# Supply.net
KiCad netlist of a schematic drawn in Altium Designer
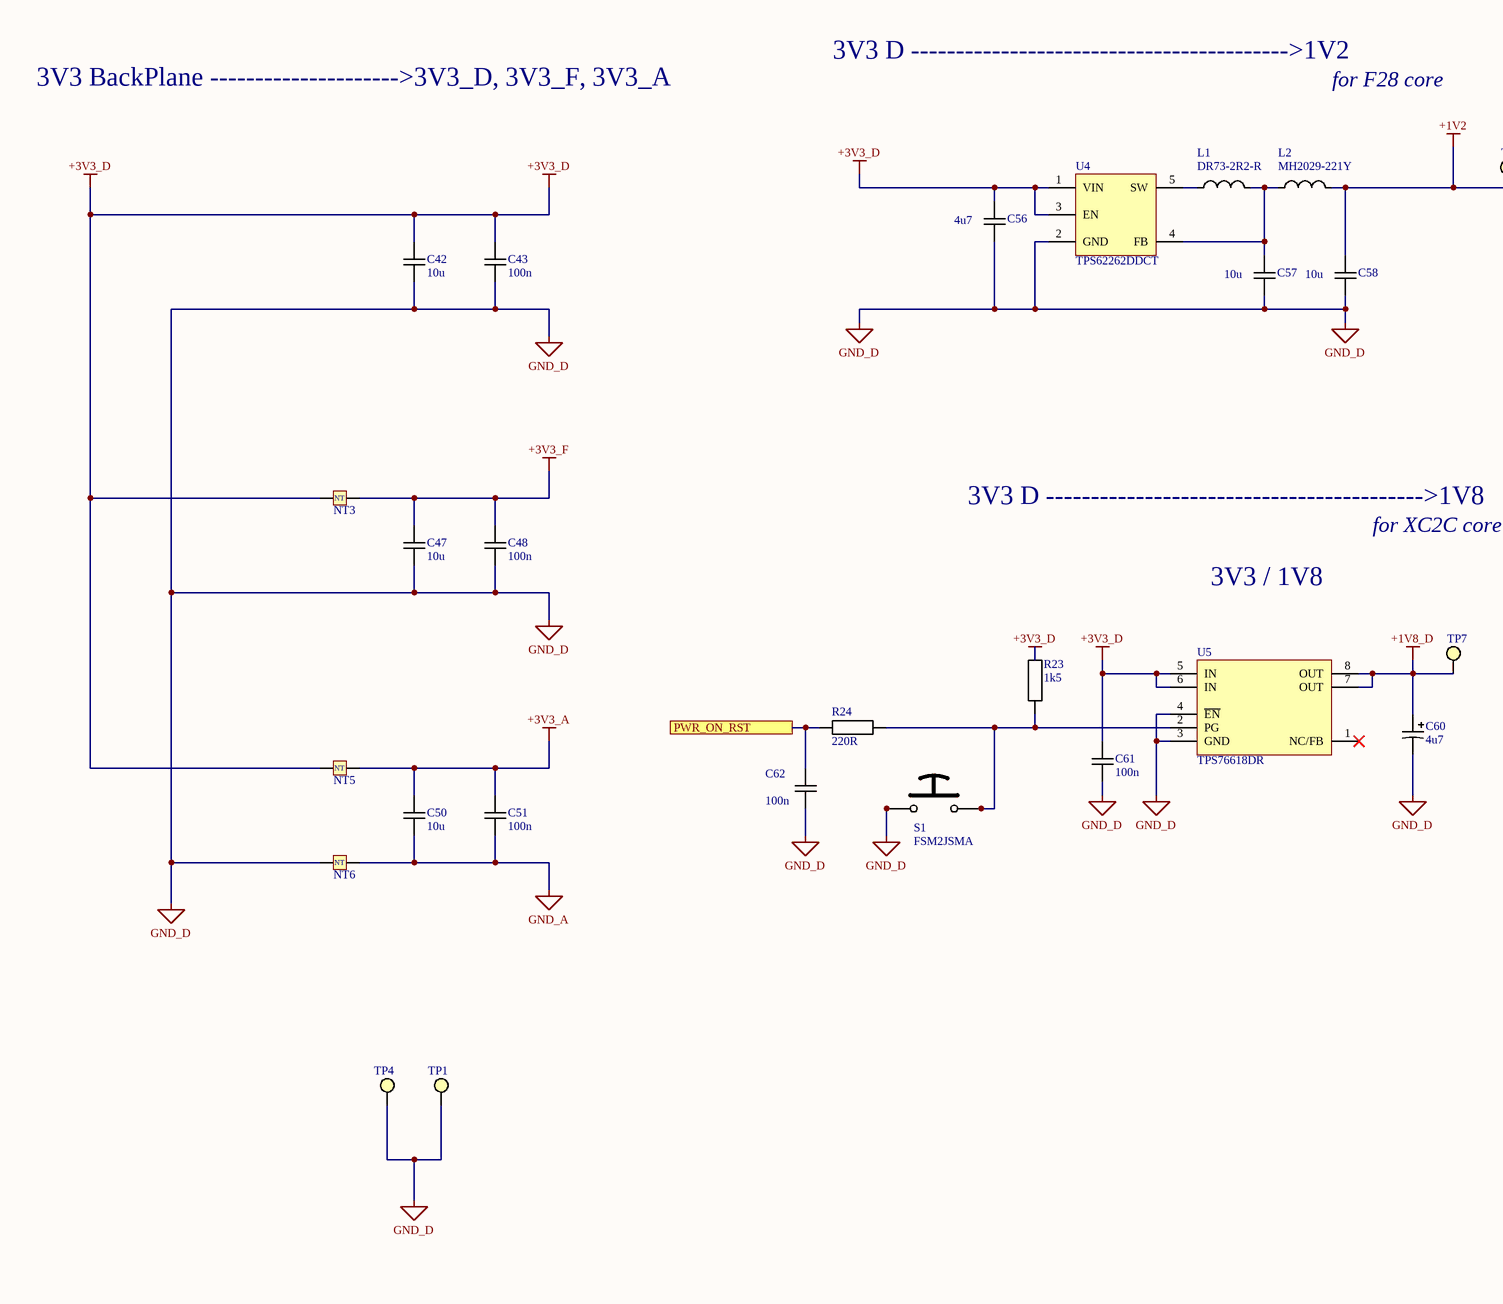
[diagram p0: Supply.SchDoc, left]
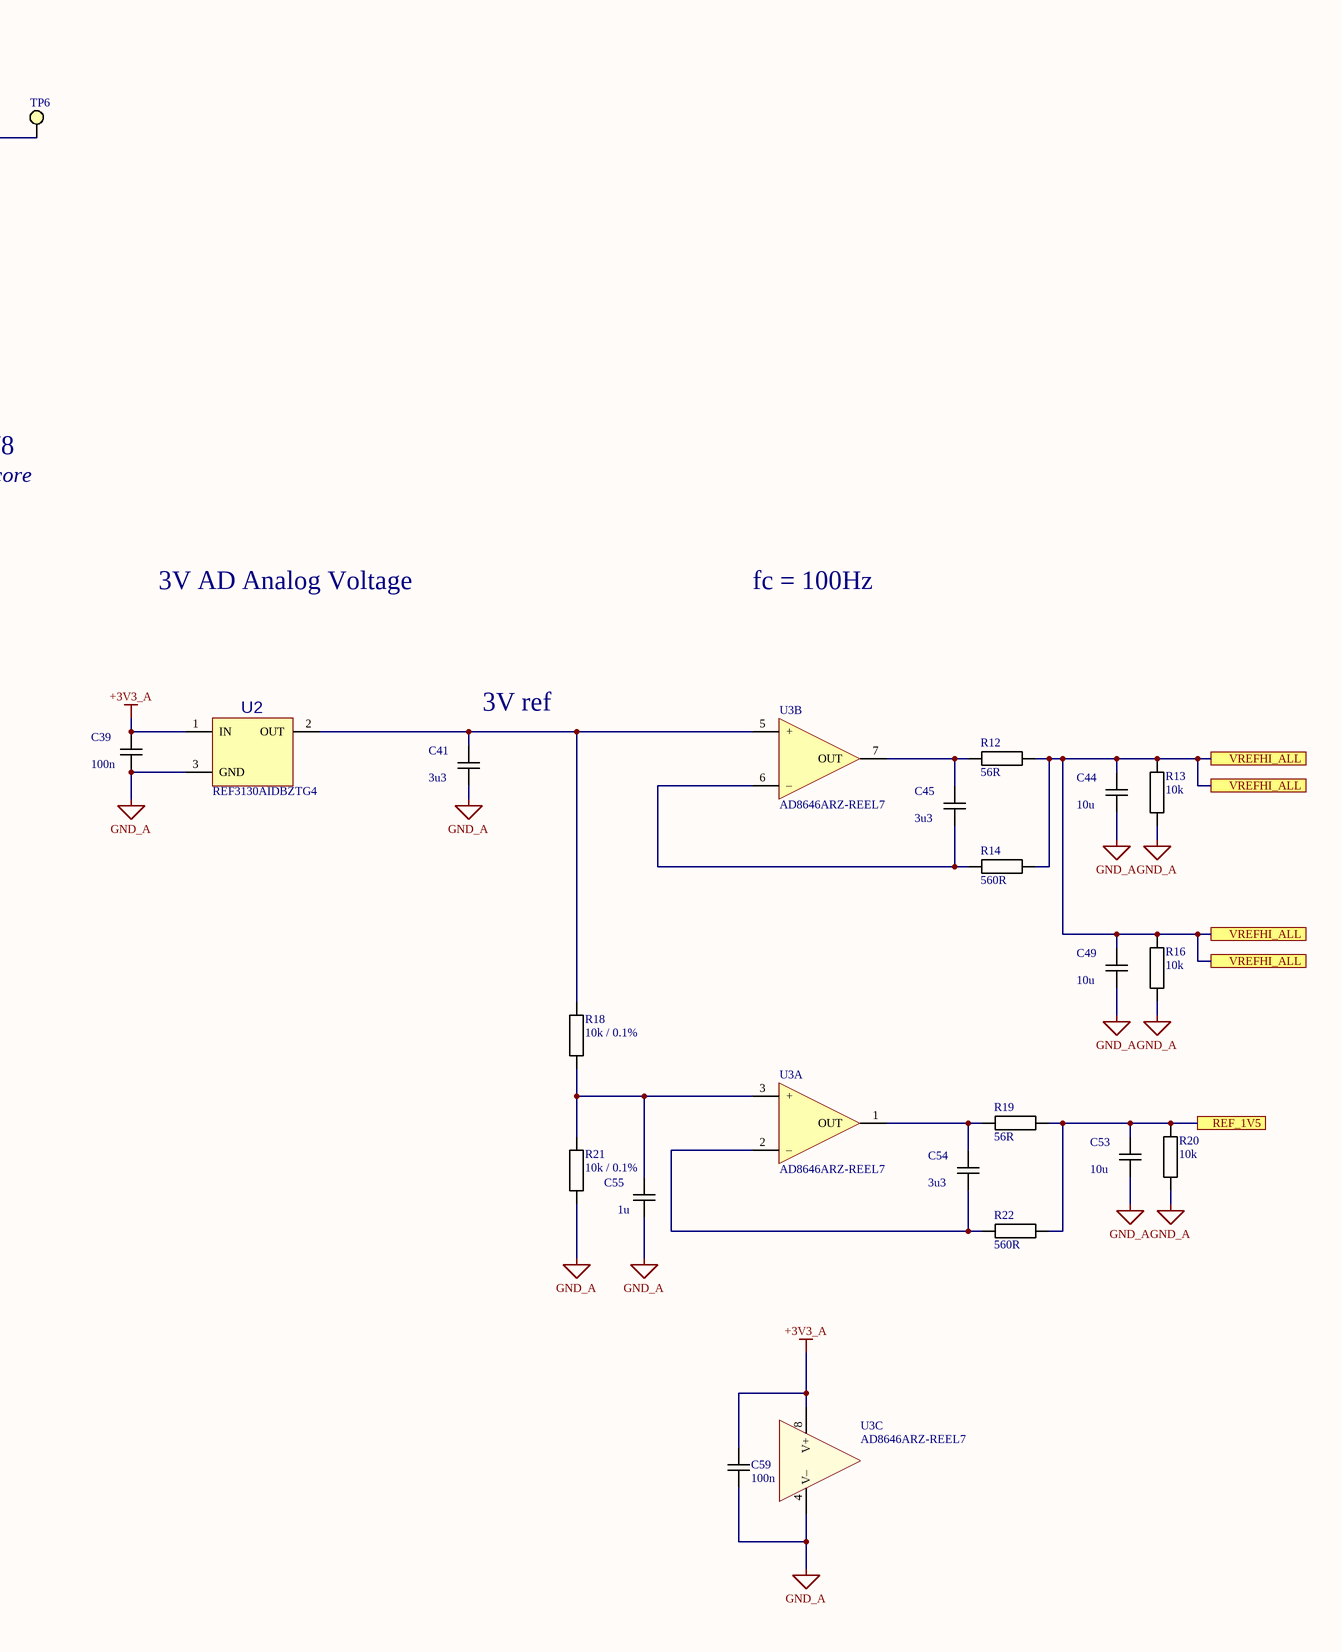
[diagram p1: Supply.SchDoc, right]

(export (version "E")
  (design (tool "Eeschema 10.0.6"))
  (components
    (comp (ref "C39")
      (value "100n")
      (footprint "CAPACITOR 1608 REFLOW")
      (description "Capacitor X7R 10% 50V 1608(0603)")
      (libsource (lib "Capacitor") (part "Capacitor"))
    )
    (comp (ref "C41")
      (value "3u3")
      (footprint "CAPACITOR 2012 REFLOW")
      (description "Capacitor X7R 10% 10V 2012(0805)")
      (libsource (lib "Capacitor") (part "Capacitor"))
    )
    (comp (ref "C42")
      (value "10u")
      (footprint "CAPACITOR 2012 REFLOW")
      (description "Capacitor X7R 10% 10V 2012(0805)")
      (libsource (lib "Capacitor") (part "Capacitor"))
    )
    (comp (ref "C43")
      (value "100n")
      (footprint "CAPACITOR 2012 REFLOW")
      (description "Capacitor X7R 10% 50V 2012(0805)")
      (libsource (lib "Capacitor") (part "Capacitor"))
    )
    (comp (ref "C44")
      (value "10u")
      (footprint "CAPACITOR 2012 REFLOW")
      (description "Capacitor X7R 10% 10V 2012(0805)")
      (libsource (lib "Capacitor") (part "Capacitor"))
    )
    (comp (ref "C45")
      (value "3u3")
      (footprint "CAPACITOR 2012 REFLOW")
      (description "Capacitor X7R 10% 10V 2012(0805)")
      (libsource (lib "Capacitor") (part "Capacitor"))
    )
    (comp (ref "C47")
      (value "10u")
      (footprint "CAPACITOR 2012 REFLOW")
      (description "Capacitor X7R 10% 10V 2012(0805)")
      (libsource (lib "Capacitor") (part "Capacitor"))
    )
    (comp (ref "C48")
      (value "100n")
      (footprint "CAPACITOR 2012 REFLOW")
      (description "Capacitor X7R 10% 50V 2012(0805)")
      (libsource (lib "Capacitor") (part "Capacitor"))
    )
    (comp (ref "C49")
      (value "10u")
      (footprint "CAPACITOR 2012 REFLOW")
      (description "Capacitor X7R 10% 10V 2012(0805)")
      (libsource (lib "Capacitor") (part "Capacitor"))
    )
    (comp (ref "C50")
      (value "10u")
      (footprint "CAPACITOR 2012 REFLOW")
      (description "Capacitor X7R 10% 10V 2012(0805)")
      (libsource (lib "Capacitor") (part "Capacitor"))
    )
    (comp (ref "C51")
      (value "100n")
      (footprint "CAPACITOR 2012 REFLOW")
      (description "Capacitor X7R 10% 50V 2012(0805)")
      (libsource (lib "Capacitor") (part "Capacitor"))
    )
    (comp (ref "C53")
      (value "10u")
      (footprint "CAPACITOR 2012 REFLOW")
      (description "Capacitor X7R 10% 10V 2012(0805)")
      (libsource (lib "Capacitor") (part "Capacitor"))
    )
    (comp (ref "C54")
      (value "3u3")
      (footprint "CAPACITOR 2012 REFLOW")
      (description "Capacitor X7R 10% 10V 2012(0805)")
      (libsource (lib "Capacitor") (part "Capacitor"))
    )
    (comp (ref "C55")
      (value "1u")
      (footprint "CAPACITOR 2012 REFLOW")
      (description "Capacitor X7R 10% 10V 2012(0805)")
      (libsource (lib "Capacitor") (part "Capacitor"))
    )
    (comp (ref "C56")
      (value "4u7")
      (footprint "CAPACITOR 2012 REFLOW")
      (description "Capacitor X7R 10% 10V 2012(0805)")
      (libsource (lib "Capacitor") (part "Capacitor"))
    )
    (comp (ref "C57")
      (value "10u")
      (footprint "CAPACITOR 2012 REFLOW")
      (description "Capacitor X7R 10% 10V 2012(0805)")
      (libsource (lib "Capacitor") (part "Capacitor"))
    )
    (comp (ref "C58")
      (value "10u")
      (footprint "CAPACITOR 2012 REFLOW")
      (description "Capacitor X7R 10% 10V 2012(0805)")
      (libsource (lib "Capacitor") (part "Capacitor"))
    )
    (comp (ref "C59")
      (value "100n")
      (footprint "CAPACITOR 1608 REFLOW")
      (description "Capacitor X7R 10% 50V 1608(0603)")
      (libsource (lib "Capacitor") (part "Capacitor"))
    )
    (comp (ref "C60")
      (value "4u7")
      (footprint "CAPACITOR POL 3528-21 REFLOW")
      (description "Capacitor Tantalum 10 % 10V 3528(1311-TAJ-B)")
      (libsource (lib "Capacitor") (part "Capacitor Polarized"))
    )
    (comp (ref "C61")
      (value "100n")
      (footprint "CAPACITOR 1608 REFLOW")
      (description "Capacitor X7R 10% 50V 1608(0603)")
      (libsource (lib "Capacitor") (part "Capacitor"))
    )
    (comp (ref "C62")
      (value "100n")
      (footprint "CAPACITOR 1608 REFLOW")
      (description "Capacitor X7R 10% 50V 1608(0603)")
      (libsource (lib "Capacitor") (part "Capacitor"))
    )
    (comp (ref "L1")
      (value "DR73-2R2-R")
      (footprint "DR73")
      (description "Inductor")
      (fields (field (name "MANUFACTURER") "Coiltronics / Eaton"))
      (libsource (lib "Inductor") (part "Inductor"))
    )
    (comp (ref "L2")
      (value "MH2029-221Y")
      (footprint "INDUCTOR 2012 REFLOW")
      (description "Inductor")
      (fields (field (name "MANUFACTURER") "Bourns"))
      (libsource (lib "Inductor") (part "Inductor"))
    )
    (comp (ref "NT3")
      (value "Net Tie")
      (footprint "NET TIE 1005")
      (description "Connection for 2 different NETNAME")
      (libsource (lib "Jumper") (part "Net Tie"))
    )
    (comp (ref "NT5")
      (value "Net Tie")
      (footprint "NET TIE 1005")
      (description "Connection for 2 different NETNAME")
      (libsource (lib "Jumper") (part "Net Tie"))
    )
    (comp (ref "NT6")
      (value "Net Tie")
      (footprint "NET TIE 1005")
      (description "Connection for 2 different NETNAME")
      (libsource (lib "Jumper") (part "Net Tie"))
    )
    (comp (ref "R12")
      (value "56R")
      (footprint "RESISTOR 1608 REFLOW")
      (description "Resistor 1% 50V 100mW 1608(0603)")
      (libsource (lib "Resistor") (part "Resistor"))
    )
    (comp (ref "R13")
      (value "10k")
      (footprint "RESISTOR 1608 REFLOW")
      (description "Resistor 1% 50V 100mW 1608(0603)")
      (libsource (lib "Resistor") (part "Resistor"))
    )
    (comp (ref "R14")
      (value "560R")
      (footprint "RESISTOR 1608 REFLOW")
      (description "Resistor 1% 50V 100mW 1608(0603)")
      (libsource (lib "Resistor") (part "Resistor"))
    )
    (comp (ref "R16")
      (value "10k")
      (footprint "RESISTOR 1608 REFLOW")
      (description "Resistor 1% 50V 100mW 1608(0603)")
      (libsource (lib "Resistor") (part "Resistor"))
    )
    (comp (ref "R18")
      (value "10k / 0.1%")
      (footprint "RESISTOR 1608 REFLOW")
      (description "Resistor 1% 50V 100mW 1608(0603)")
      (libsource (lib "Resistor") (part "Resistor"))
    )
    (comp (ref "R19")
      (value "56R")
      (footprint "RESISTOR 1608 REFLOW")
      (description "Resistor 1% 50V 100mW 1608(0603)")
      (libsource (lib "Resistor") (part "Resistor"))
    )
    (comp (ref "R20")
      (value "10k")
      (footprint "RESISTOR 1608 REFLOW")
      (description "Resistor 1% 50V 100mW 1608(0603)")
      (libsource (lib "Resistor") (part "Resistor"))
    )
    (comp (ref "R21")
      (value "10k / 0.1%")
      (footprint "RESISTOR 1608 REFLOW")
      (description "Resistor 1% 50V 100mW 1608(0603)")
      (libsource (lib "Resistor") (part "Resistor"))
    )
    (comp (ref "R22")
      (value "560R")
      (footprint "RESISTOR 1608 REFLOW")
      (description "Resistor 1% 50V 100mW 1608(0603)")
      (libsource (lib "Resistor") (part "Resistor"))
    )
    (comp (ref "R23")
      (value "1k5")
      (footprint "RESISTOR 1608 REFLOW")
      (description "Resistor 1% 50V 100mW 1608(0603)")
      (libsource (lib "Resistor") (part "Resistor"))
    )
    (comp (ref "R24")
      (value "220R")
      (footprint "RESISTOR 1608 REFLOW")
      (description "Resistor 1% 50V 100mW 1608(0603)")
      (libsource (lib "Resistor") (part "Resistor"))
    )
    (comp (ref "S1")
      (value "FSM2JSMA")
      (footprint "Push Button C6.0x6.0 TE FSM-2J-SMA")
      (description "Push Button, 4 pins, 2 poles parrallèle")
      (fields (field (name "MANUFACTURER") "TE Connectivity / Alcoswitch"))
      (libsource (lib "Button") (part "Push Button 4Pins"))
    )
    (comp (ref "TP1")
      (value "*")
      (footprint "Test Point Keystone Miniature BLACK")
      (description "Test Point")
      (libsource (lib "Testpoint") (part "Test Point"))
    )
    (comp (ref "TP4")
      (value "*")
      (footprint "Test Point Keystone Miniature BLACK")
      (description "Test Point")
      (libsource (lib "Testpoint") (part "Test Point"))
    )
    (comp (ref "TP6")
      (value "*")
      (footprint "Hole 1.0 D2.0")
      (description "Hole")
      (libsource (lib "Testpoint") (part "Hole"))
    )
    (comp (ref "TP7")
      (value "*")
      (footprint "Hole 1.0 D2.0")
      (description "Hole")
      (libsource (lib "Testpoint") (part "Hole"))
    )
    (comp (ref "U2")
      (value "REF3130AIDBZTG4")
      (footprint "SOT23 P0.95 C1.6x3.0 H1.3")
      (description "Generic Positive Voltage Reference")
      (fields (field (name "MANUFACTURER") "Texas Instruments"))
      (libsource (lib "Regulator") (part "REFERENCE SOT23 IN-OUT- GND"))
    )
    (comp (ref "U3")
      (value "AD8646ARZ-REEL7")
      (footprint "SO8 P1.27 C4.0X5.0 H1.75")
      (description "Generic dual OPA 8 pins")
      (fields (field (name "MANUFACTURER") "Analog Devices"))
      (libsource (lib "Amplifier") (part "OPA DUAL"))
    )
    (comp (ref "U4")
      (value "TPS62262DDCT")
      (footprint "SOT23-5 P0.95 C1.6x3.0 H1.3")
      (description "2.25-MHz 600-mA Step Down Converter in 2 x 2 SOT Package")
      (fields (field (name "MANUFACTURER") "Texas Instruments"))
      (libsource (lib "VoltageConverter") (part "TPS6226x"))
    )
    (comp (ref "U5")
      (value "TPS76618DR")
      (footprint "SO8 P1.27 C4.0X5.0 H1.75")
      (description "Ultra Low Quiescent Current 250mA, Low Dropout Regulator")
      (fields (field (name "MANUFACTURER") "Texas Instruments"))
      (libsource (lib "Regulator") (part "TPS766__D"))
    )
  )
  (nets
    (net (code "1") (name "+1V2") (class "Default")
      (node (ref "C58") (pin "2") (pinfunction "2_2") (pintype "passive"))
      (node (ref "L2") (pin "2") (pinfunction "2_2") (pintype "passive"))
      (node (ref "TP6") (pin "1") (pinfunction "1_1") (pintype "passive"))
    )
    (net (code "2") (name "+1V8_D") (class "Default")
      (node (ref "C60") (pin "1") (pinfunction "1_1") (pintype "passive"))
      (node (ref "TP7") (pin "1") (pinfunction "1_1") (pintype "passive"))
      (node (ref "U5") (pin "7") (pinfunction "OUT_7") (pintype "passive"))
      (node (ref "U5") (pin "8") (pinfunction "OUT_8") (pintype "passive"))
    )
    (net (code "3") (name "+3V3_A") (class "Default")
      (node (ref "C39") (pin "2") (pinfunction "2_2") (pintype "passive"))
      (node (ref "C50") (pin "1") (pinfunction "1_1") (pintype "passive"))
      (node (ref "C51") (pin "1") (pinfunction "1_1") (pintype "passive"))
      (node (ref "C59") (pin "2") (pinfunction "2_2") (pintype "passive"))
      (node (ref "NT5") (pin "2") (pinfunction "2_2") (pintype "passive"))
      (node (ref "U2") (pin "1") (pinfunction "IN_1") (pintype "passive"))
      (node (ref "U3") (pin "8") (pinfunction "V+_8") (pintype "passive"))
    )
    (net (code "4") (name "+3V3_D") (class "Default")
      (node (ref "C42") (pin "1") (pinfunction "1_1") (pintype "passive"))
      (node (ref "C43") (pin "1") (pinfunction "1_1") (pintype "passive"))
      (node (ref "C56") (pin "2") (pinfunction "2_2") (pintype "passive"))
      (node (ref "C61") (pin "1") (pinfunction "1_1") (pintype "passive"))
      (node (ref "NT3") (pin "1") (pinfunction "1_1") (pintype "passive"))
      (node (ref "NT5") (pin "1") (pinfunction "1_1") (pintype "passive"))
      (node (ref "R23") (pin "2") (pinfunction "2_2") (pintype "passive"))
      (node (ref "U4") (pin "1") (pinfunction "VIN_1") (pintype "passive"))
      (node (ref "U4") (pin "3") (pinfunction "EN_3") (pintype "passive"))
      (node (ref "U5") (pin "5") (pinfunction "IN_5") (pintype "passive"))
      (node (ref "U5") (pin "6") (pinfunction "IN_6") (pintype "passive"))
    )
    (net (code "5") (name "+3V3_F") (class "Default")
      (node (ref "C47") (pin "1") (pinfunction "1_1") (pintype "passive"))
      (node (ref "C48") (pin "1") (pinfunction "1_1") (pintype "passive"))
      (node (ref "NT3") (pin "2") (pinfunction "2_2") (pintype "passive"))
    )
    (net (code "6") (name "/PWR_ON_RST") (class "Default")
      (node (ref "C62") (pin "2") (pinfunction "2_2") (pintype "passive"))
      (node (ref "R24") (pin "1") (pinfunction "1_1") (pintype "passive"))
    )
    (net (code "7") (name "/REF_1V5") (class "Default")
      (node (ref "C53") (pin "2") (pinfunction "2_2") (pintype "passive"))
      (node (ref "R19") (pin "1") (pinfunction "1_1") (pintype "passive"))
      (node (ref "R20") (pin "1") (pinfunction "1_1") (pintype "passive"))
      (node (ref "R22") (pin "1") (pinfunction "1_1") (pintype "passive"))
    )
    (net (code "8") (name "/VREFHI_ALL") (class "Default")
      (node (ref "C44") (pin "2") (pinfunction "2_2") (pintype "passive"))
      (node (ref "C49") (pin "2") (pinfunction "2_2") (pintype "passive"))
      (node (ref "R12") (pin "1") (pinfunction "1_1") (pintype "passive"))
      (node (ref "R13") (pin "1") (pinfunction "1_1") (pintype "passive"))
      (node (ref "R14") (pin "1") (pinfunction "1_1") (pintype "passive"))
      (node (ref "R16") (pin "1") (pinfunction "1_1") (pintype "passive"))
    )
    (net (code "9") (name "GND_A") (class "Default")
      (node (ref "C39") (pin "1") (pinfunction "1_1") (pintype "passive"))
      (node (ref "C41") (pin "1") (pinfunction "1_1") (pintype "passive"))
      (node (ref "C44") (pin "1") (pinfunction "1_1") (pintype "passive"))
      (node (ref "C49") (pin "1") (pinfunction "1_1") (pintype "passive"))
      (node (ref "C50") (pin "2") (pinfunction "2_2") (pintype "passive"))
      (node (ref "C51") (pin "2") (pinfunction "2_2") (pintype "passive"))
      (node (ref "C53") (pin "1") (pinfunction "1_1") (pintype "passive"))
      (node (ref "C55") (pin "1") (pinfunction "1_1") (pintype "passive"))
      (node (ref "C59") (pin "1") (pinfunction "1_1") (pintype "passive"))
      (node (ref "NT6") (pin "2") (pinfunction "2_2") (pintype "passive"))
      (node (ref "R13") (pin "2") (pinfunction "2_2") (pintype "passive"))
      (node (ref "R16") (pin "2") (pinfunction "2_2") (pintype "passive"))
      (node (ref "R20") (pin "2") (pinfunction "2_2") (pintype "passive"))
      (node (ref "R21") (pin "2") (pinfunction "2_2") (pintype "passive"))
      (node (ref "U2") (pin "3") (pinfunction "GND_3") (pintype "passive"))
      (node (ref "U3") (pin "4") (pinfunction "V–_4") (pintype "passive"))
    )
    (net (code "10") (name "GND_D") (class "Default")
      (node (ref "C42") (pin "2") (pinfunction "2_2") (pintype "passive"))
      (node (ref "C43") (pin "2") (pinfunction "2_2") (pintype "passive"))
      (node (ref "C47") (pin "2") (pinfunction "2_2") (pintype "passive"))
      (node (ref "C48") (pin "2") (pinfunction "2_2") (pintype "passive"))
      (node (ref "C56") (pin "1") (pinfunction "1_1") (pintype "passive"))
      (node (ref "C57") (pin "1") (pinfunction "1_1") (pintype "passive"))
      (node (ref "C58") (pin "1") (pinfunction "1_1") (pintype "passive"))
      (node (ref "C60") (pin "2") (pinfunction "2_2") (pintype "passive"))
      (node (ref "C61") (pin "2") (pinfunction "2_2") (pintype "passive"))
      (node (ref "C62") (pin "1") (pinfunction "1_1") (pintype "passive"))
      (node (ref "NT6") (pin "1") (pinfunction "1_1") (pintype "passive"))
      (node (ref "S1") (pin "1") (pinfunction "1_1") (pintype "passive"))
      (node (ref "S1") (pin "2") (pinfunction "2_2") (pintype "passive"))
      (node (ref "TP1") (pin "1") (pinfunction "1_1") (pintype "passive"))
      (node (ref "TP4") (pin "1") (pinfunction "1_1") (pintype "passive"))
      (node (ref "U4") (pin "2") (pinfunction "GND_2") (pintype "passive"))
      (node (ref "U5") (pin "3") (pinfunction "GND_3") (pintype "passive"))
      (node (ref "U5") (pin "4") (pinfunction "~{EN}_4") (pintype "passive"))
    )
    (net (code "11") (name "Net-(U2-OUT)") (class "Default")
      (node (ref "C41") (pin "2") (pinfunction "2_2") (pintype "passive"))
      (node (ref "R18") (pin "2") (pinfunction "2_2") (pintype "passive"))
      (node (ref "U2") (pin "2") (pinfunction "OUT_2") (pintype "passive"))
      (node (ref "U3") (pin "5") (pinfunction "+_5") (pintype "passive"))
    )
    (net (code "12") (name "Net-(U3A-+)") (class "Default")
      (node (ref "C55") (pin "2") (pinfunction "2_2") (pintype "passive"))
      (node (ref "R18") (pin "1") (pinfunction "1_1") (pintype "passive"))
      (node (ref "R21") (pin "1") (pinfunction "1_1") (pintype "passive"))
      (node (ref "U3") (pin "3") (pinfunction "+_3") (pintype "passive"))
    )
    (net (code "13") (name "Net-(U3A-OUT)") (class "Default")
      (node (ref "C54") (pin "2") (pinfunction "2_2") (pintype "passive"))
      (node (ref "R19") (pin "2") (pinfunction "2_2") (pintype "passive"))
      (node (ref "U3") (pin "1") (pinfunction "OUT_1") (pintype "passive"))
    )
    (net (code "14") (name "Net-(U3A-–)") (class "Default")
      (node (ref "C54") (pin "1") (pinfunction "1_1") (pintype "passive"))
      (node (ref "R22") (pin "2") (pinfunction "2_2") (pintype "passive"))
      (node (ref "U3") (pin "2") (pinfunction "–_2") (pintype "passive"))
    )
    (net (code "15") (name "Net-(U3B-OUT)") (class "Default")
      (node (ref "C45") (pin "2") (pinfunction "2_2") (pintype "passive"))
      (node (ref "R12") (pin "2") (pinfunction "2_2") (pintype "passive"))
      (node (ref "U3") (pin "7") (pinfunction "OUT_7") (pintype "passive"))
    )
    (net (code "16") (name "Net-(U3B-–)") (class "Default")
      (node (ref "C45") (pin "1") (pinfunction "1_1") (pintype "passive"))
      (node (ref "R14") (pin "2") (pinfunction "2_2") (pintype "passive"))
      (node (ref "U3") (pin "6") (pinfunction "–_6") (pintype "passive"))
    )
    (net (code "17") (name "Net-(U4-FB)") (class "Default")
      (node (ref "C57") (pin "2") (pinfunction "2_2") (pintype "passive"))
      (node (ref "L1") (pin "2") (pinfunction "2_2") (pintype "passive"))
      (node (ref "L2") (pin "1") (pinfunction "1_1") (pintype "passive"))
      (node (ref "U4") (pin "4") (pinfunction "FB_4") (pintype "passive"))
    )
    (net (code "18") (name "Net-(U4-SW)") (class "Default")
      (node (ref "L1") (pin "1") (pinfunction "1_1") (pintype "passive"))
      (node (ref "U4") (pin "5") (pinfunction "SW_5") (pintype "passive"))
    )
    (net (code "19") (name "Net-(U5-PG)") (class "Default")
      (node (ref "R23") (pin "1") (pinfunction "1_1") (pintype "passive"))
      (node (ref "R24") (pin "2") (pinfunction "2_2") (pintype "passive"))
      (node (ref "S1") (pin "3") (pinfunction "3_3") (pintype "passive"))
      (node (ref "S1") (pin "4") (pinfunction "4_4") (pintype "passive"))
      (node (ref "U5") (pin "2") (pinfunction "PG_2") (pintype "passive"))
    )
    (net (code "20") (name "unconnected-(U5-NC{slash}FB-Pad1)") (class "Default")
      (node (ref "U5") (pin "1") (pinfunction "NC/FB_1") (pintype "passive+no_connect"))
    )
  )
)
